# Sheet1.net
KiCad netlist of a schematic drawn in Altium Designer
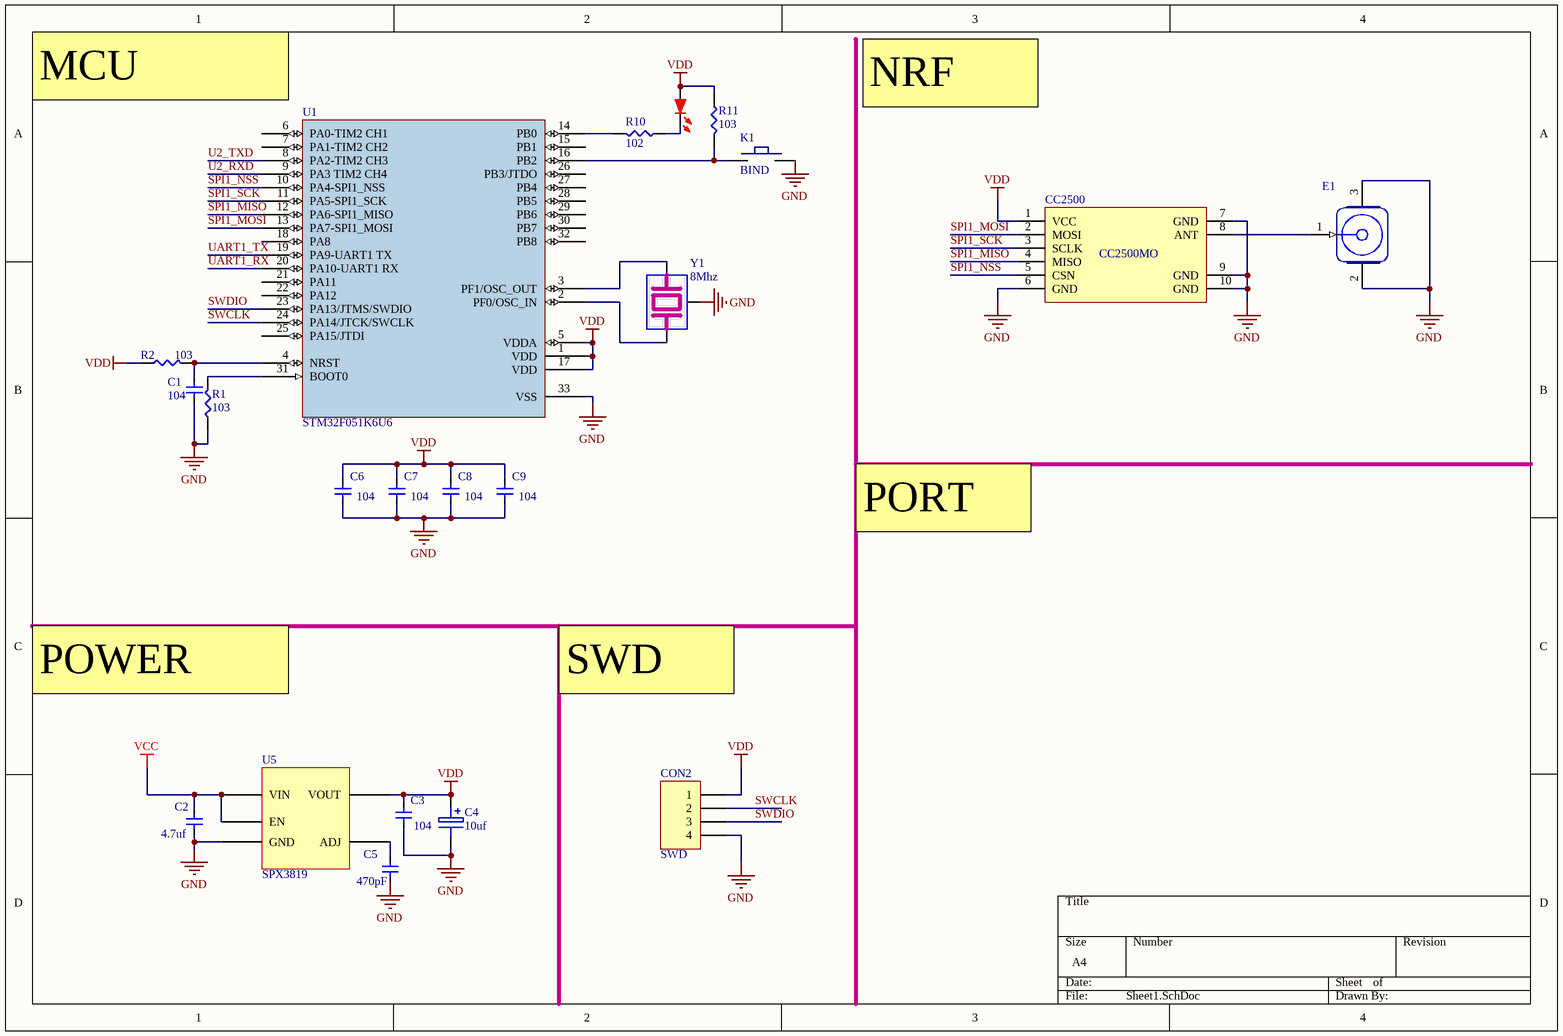
[diagram p0: Sheet1.SchDoc]

(export (version "E")
  (design (tool "Eeschema 10.0.6"))
  (components
    (comp (ref "C1")
      (value "104")
      (footprint "JL_PCB:0603C")
      (description "Capacitor")
      (libsource (lib "BASIC Devices") (part "CAP"))
    )
    (comp (ref "C2")
      (value "4.7uf")
      (footprint "JL_PCB:0603C")
      (description "Capacitor")
      (libsource (lib "BASIC Devices") (part "CAP"))
    )
    (comp (ref "C3")
      (value "104")
      (footprint "0603C")
      (description "Capacitor")
      (libsource (lib "BASIC Devices") (part "CAP"))
    )
    (comp (ref "C4")
      (value "10uf")
      (footprint "JL_PCB:1206C")
      (description "Electrolytic Capacitor")
      (libsource (lib "BASIC Devices") (part "ELECTRO1"))
    )
    (comp (ref "C5")
      (value "470pF")
      (footprint "JL_PCB:0603C")
      (description "Capacitor")
      (libsource (lib "BASIC Devices") (part "CAP"))
    )
    (comp (ref "C6")
      (value "104")
      (footprint "JL_PCB:0603C")
      (description "Capacitor")
      (libsource (lib "BASIC Devices") (part "CAP"))
    )
    (comp (ref "C7")
      (value "104")
      (footprint "JL_PCB:0603C")
      (description "Capacitor")
      (libsource (lib "BASIC Devices") (part "CAP"))
    )
    (comp (ref "C8")
      (value "104")
      (footprint "JL_PCB:0603C")
      (description "Capacitor")
      (libsource (lib "BASIC Devices") (part "CAP"))
    )
    (comp (ref "C9")
      (value "104")
      (footprint "JL_PCB:0603C")
      (description "Capacitor")
      (libsource (lib "BASIC Devices") (part "CAP"))
    )
    (comp (ref "CC2500") (value "CC2500") (libsource (lib "FrSky_Rx_Mini") (part "CC2500")))
    (comp (ref "CON2")
      (value "SWD")
      (footprint "HDR1X4")
      (description "Header, 4-Pin")
      (fields (field (name "PUBLISHER") "Altium Limited"))
      (libsource (lib "3D") (part "Header 4"))
    )
    (comp (ref "D1") (value "LED-R") (footprint "0603C") (libsource (lib "JL_SCH") (part "LED-R")))
    (comp (ref "E1")
      (value "U.FL-LP Hirose Micro RF Connector")
      (footprint "U.FL-LP(V)-040")
      (description "Hirose U.FL-LP(V)-040  Micro RF connector,  50 Ohm Impedance")
      (fields (field (name "MANUFACTURER") "Hirose"))
      (libsource (lib "RF Connectors") (part "U.FL-LP(V)-040"))
    )
    (comp (ref "K1") (value "BIND") (footprint "KEY_3x3x2mm") (libsource (lib "My_lib_wjt") (part "KEY")))
    (comp (ref "R1") (value "103") (footprint "JL_PCB:0603R") (libsource (lib "BASIC Devices") (part "RES0")))
    (comp (ref "R2") (value "103") (footprint "JL_PCB:0603R") (libsource (lib "BASIC Devices") (part "RES0")))
    (comp (ref "R10")
      (value "102")
      (footprint "JL_PCB:0603R")
      (libsource (lib "BASIC Devices") (part "RES0"))
    )
    (comp (ref "R11")
      (value "103")
      (footprint "JL_PCB:0603R")
      (libsource (lib "BASIC Devices") (part "RES0"))
    )
    (comp (ref "U1")
      (value "STM32F051K6U6")
      (footprint "QFN32_1GND")
      (description "STM32 ARM-based 32-bit MCU with 128 Kbytes Flash, 48-pin LQFP, Industrial Temperature")
      (fields (field (name "PUBLISHER") "Altium Limited"))
      (libsource (lib "PCB_Project") (part "STM32F103CBT6"))
    )
    (comp (ref "U5") (value "SPX3819") (footprint "SOT-23-5") (libsource (lib "minifly") (part "SPX3819")))
    (comp (ref "Y1") (value "8Mhz") (footprint "XTAL_mini") (libsource (lib "minifly") (part "XTAL")))
  )
  (nets
    (net (code "1") (name "/SPI1_MISO") (class "Default")
      (node (ref "CC2500") (pin "4") (pinfunction "MISO_4") (pintype "passive"))
      (node (ref "U1") (pin "12") (pinfunction "PA6-SPI1_MISO_12") (pintype "bidirectional"))
    )
    (net (code "2") (name "/SPI1_MOSI") (class "Default")
      (node (ref "CC2500") (pin "2") (pinfunction "MOSI_2") (pintype "passive"))
      (node (ref "U1") (pin "13") (pinfunction "PA7-SPI1_MOSI_13") (pintype "bidirectional"))
    )
    (net (code "3") (name "/SPI1_NSS") (class "Default")
      (node (ref "CC2500") (pin "5") (pinfunction "CSN_5") (pintype "passive"))
      (node (ref "U1") (pin "10") (pinfunction "PA4-SPI1_NSS_10") (pintype "bidirectional"))
    )
    (net (code "4") (name "/SPI1_SCK") (class "Default")
      (node (ref "CC2500") (pin "3") (pinfunction "SCLK_3") (pintype "passive"))
      (node (ref "U1") (pin "11") (pinfunction "PA5-SPI1_SCK_11") (pintype "bidirectional"))
    )
    (net (code "5") (name "/SWCLK") (class "Default")
      (node (ref "CON2") (pin "2") (pinfunction "2_2") (pintype "passive"))
      (node (ref "U1") (pin "24") (pinfunction "PA14/JTCK/SWCLK_24") (pintype "bidirectional"))
    )
    (net (code "6") (name "/SWDIO") (class "Default")
      (node (ref "CON2") (pin "3") (pinfunction "3_3") (pintype "passive"))
      (node (ref "U1") (pin "23") (pinfunction "PA13/JTMS/SWDIO_23") (pintype "bidirectional"))
    )
    (net (code "7") (name "/U2_RXD") (class "Default")
      (node (ref "U1") (pin "9") (pinfunction "PA3_TIM2_CH4_9") (pintype "bidirectional"))
    )
    (net (code "8") (name "/U2_TXD") (class "Default")
      (node (ref "U1") (pin "8") (pinfunction "PA2-TIM2_CH3_8") (pintype "bidirectional"))
    )
    (net (code "9") (name "/UART1_RX") (class "Default")
      (node (ref "U1") (pin "20") (pinfunction "PA10-UART1_RX_20") (pintype "bidirectional"))
    )
    (net (code "10") (name "/UART1_TX") (class "Default")
      (node (ref "U1") (pin "19") (pinfunction "PA9-UART1_TX_19") (pintype "bidirectional"))
    )
    (net (code "11") (name "GND") (class "Default")
      (node (ref "C1") (pin "2") (pinfunction "2_2") (pintype "passive"))
      (node (ref "C2") (pin "2") (pinfunction "2_2") (pintype "passive"))
      (node (ref "C3") (pin "2") (pinfunction "2_2") (pintype "passive"))
      (node (ref "C4") (pin "2") (pinfunction "2_2") (pintype "passive"))
      (node (ref "C5") (pin "2") (pinfunction "2_2") (pintype "passive"))
      (node (ref "C6") (pin "2") (pinfunction "2_2") (pintype "passive"))
      (node (ref "C7") (pin "2") (pinfunction "2_2") (pintype "passive"))
      (node (ref "C8") (pin "2") (pinfunction "2_2") (pintype "passive"))
      (node (ref "C9") (pin "2") (pinfunction "2_2") (pintype "passive"))
      (node (ref "CC2500") (pin "10") (pinfunction "GND_10") (pintype "passive"))
      (node (ref "CC2500") (pin "6") (pinfunction "GND_6") (pintype "passive"))
      (node (ref "CC2500") (pin "7") (pinfunction "GND_7") (pintype "passive"))
      (node (ref "CC2500") (pin "9") (pinfunction "GND_9") (pintype "passive"))
      (node (ref "CON2") (pin "4") (pinfunction "4_4") (pintype "passive"))
      (node (ref "E1") (pin "2") (pinfunction "GND_2") (pintype "power_in"))
      (node (ref "E1") (pin "3") (pinfunction "GND_3") (pintype "power_in"))
      (node (ref "K1") (pin "2") (pinfunction "2_2") (pintype "passive"))
      (node (ref "R1") (pin "1") (pinfunction "1_1") (pintype "passive"))
      (node (ref "U1") (pin "33") (pinfunction "VSS_33") (pintype "power_in"))
      (node (ref "U5") (pin "2") (pinfunction "GND_2") (pintype "passive"))
      (node (ref "Y1") (pin "2") (pinfunction "2_2") (pintype "passive"))
    )
    (net (code "12") (name "Net-(CC2500-ANT)") (class "Default")
      (node (ref "CC2500") (pin "8") (pinfunction "ANT_8") (pintype "passive"))
      (node (ref "E1") (pin "1") (pinfunction "Signal_1") (pintype "input"))
    )
    (net (code "13") (name "Net-(D1-K)") (class "Default")
      (node (ref "D1") (pin "2") (pinfunction "K_2") (pintype "passive"))
      (node (ref "R10") (pin "1") (pinfunction "1_1") (pintype "passive"))
    )
    (net (code "14") (name "Net-(U1-BOOT0)") (class "Default")
      (node (ref "R1") (pin "2") (pinfunction "2_2") (pintype "passive"))
      (node (ref "U1") (pin "31") (pinfunction "BOOT0_31") (pintype "input"))
    )
    (net (code "15") (name "Net-(U1-NRST)") (class "Default")
      (node (ref "C1") (pin "1") (pinfunction "1_1") (pintype "passive"))
      (node (ref "R2") (pin "2") (pinfunction "2_2") (pintype "passive"))
      (node (ref "U1") (pin "4") (pinfunction "NRST_4") (pintype "bidirectional"))
    )
    (net (code "16") (name "Net-(U1-PB0)") (class "Default")
      (node (ref "R10") (pin "2") (pinfunction "2_2") (pintype "passive"))
      (node (ref "U1") (pin "14") (pinfunction "PB0_14") (pintype "bidirectional"))
    )
    (net (code "17") (name "Net-(U1-PB2)") (class "Default")
      (node (ref "K1") (pin "1") (pinfunction "1_1") (pintype "passive"))
      (node (ref "R11") (pin "2") (pinfunction "2_2") (pintype "passive"))
      (node (ref "U1") (pin "16") (pinfunction "PB2_16") (pintype "bidirectional"))
    )
    (net (code "18") (name "Net-(U1-PF0{slash}OSC_IN)") (class "Default")
      (node (ref "U1") (pin "2") (pinfunction "PF0/OSC_IN_2") (pintype "bidirectional"))
      (node (ref "Y1") (pin "1") (pinfunction "1_1") (pintype "passive"))
    )
    (net (code "19") (name "Net-(U1-PF1{slash}OSC_OUT)") (class "Default")
      (node (ref "U1") (pin "3") (pinfunction "PF1/OSC_OUT_3") (pintype "bidirectional"))
      (node (ref "Y1") (pin "3") (pinfunction "3_3") (pintype "passive"))
    )
    (net (code "20") (name "Net-(U5-ADJ)") (class "Default")
      (node (ref "C5") (pin "1") (pinfunction "1_1") (pintype "passive"))
      (node (ref "U5") (pin "4") (pinfunction "ADJ_4") (pintype "passive"))
    )
    (net (code "21") (name "VCC") (class "Default")
      (node (ref "C2") (pin "1") (pinfunction "1_1") (pintype "passive"))
      (node (ref "U5") (pin "1") (pinfunction "VIN_1") (pintype "passive"))
      (node (ref "U5") (pin "3") (pinfunction "EN_3") (pintype "passive"))
    )
    (net (code "22") (name "VDD") (class "Default")
      (node (ref "C3") (pin "1") (pinfunction "1_1") (pintype "passive"))
      (node (ref "C4") (pin "1") (pinfunction "1_1") (pintype "passive"))
      (node (ref "C6") (pin "1") (pinfunction "1_1") (pintype "passive"))
      (node (ref "C7") (pin "1") (pinfunction "1_1") (pintype "passive"))
      (node (ref "C8") (pin "1") (pinfunction "1_1") (pintype "passive"))
      (node (ref "C9") (pin "1") (pinfunction "1_1") (pintype "passive"))
      (node (ref "CC2500") (pin "1") (pinfunction "VCC_1") (pintype "passive"))
      (node (ref "CON2") (pin "1") (pinfunction "1_1") (pintype "passive"))
      (node (ref "D1") (pin "1") (pinfunction "A_1") (pintype "passive"))
      (node (ref "R11") (pin "1") (pinfunction "1_1") (pintype "passive"))
      (node (ref "R2") (pin "1") (pinfunction "1_1") (pintype "passive"))
      (node (ref "U1") (pin "1") (pinfunction "VDD_1") (pintype "power_in"))
      (node (ref "U1") (pin "17") (pinfunction "VDD_17") (pintype "power_in"))
      (node (ref "U1") (pin "5") (pinfunction "VDDA_5") (pintype "bidirectional"))
      (node (ref "U5") (pin "5") (pinfunction "VOUT_5") (pintype "passive"))
    )
    (net (code "23") (name "unconnected-(U1-PA0-TIM2_CH1-Pad6)") (class "Default")
      (node (ref "U1") (pin "6") (pinfunction "PA0-TIM2_CH1_6") (pintype "bidirectional"))
    )
    (net (code "24") (name "unconnected-(U1-PA1-TIM2_CH2-Pad7)") (class "Default")
      (node (ref "U1") (pin "7") (pinfunction "PA1-TIM2_CH2_7") (pintype "bidirectional"))
    )
    (net (code "25") (name "unconnected-(U1-PA8-Pad18)") (class "Default")
      (node (ref "U1") (pin "18") (pinfunction "PA8_18") (pintype "bidirectional"))
    )
    (net (code "26") (name "unconnected-(U1-PA11-Pad21)") (class "Default")
      (node (ref "U1") (pin "21") (pinfunction "PA11_21") (pintype "bidirectional"))
    )
    (net (code "27") (name "unconnected-(U1-PA12-Pad22)") (class "Default")
      (node (ref "U1") (pin "22") (pinfunction "PA12_22") (pintype "bidirectional"))
    )
    (net (code "28") (name "unconnected-(U1-PA15{slash}JTDI-Pad25)") (class "Default")
      (node (ref "U1") (pin "25") (pinfunction "PA15/JTDI_25") (pintype "bidirectional"))
    )
    (net (code "29") (name "unconnected-(U1-PB1-Pad15)") (class "Default")
      (node (ref "U1") (pin "15") (pinfunction "PB1_15") (pintype "bidirectional"))
    )
    (net (code "30") (name "unconnected-(U1-PB3{slash}JTDO-Pad26)") (class "Default")
      (node (ref "U1") (pin "26") (pinfunction "PB3/JTDO_26") (pintype "bidirectional"))
    )
    (net (code "31") (name "unconnected-(U1-PB4-Pad27)") (class "Default")
      (node (ref "U1") (pin "27") (pinfunction "PB4_27") (pintype "bidirectional"))
    )
    (net (code "32") (name "unconnected-(U1-PB5-Pad28)") (class "Default")
      (node (ref "U1") (pin "28") (pinfunction "PB5_28") (pintype "bidirectional"))
    )
    (net (code "33") (name "unconnected-(U1-PB6-Pad29)") (class "Default")
      (node (ref "U1") (pin "29") (pinfunction "PB6_29") (pintype "bidirectional"))
    )
    (net (code "34") (name "unconnected-(U1-PB7-Pad30)") (class "Default")
      (node (ref "U1") (pin "30") (pinfunction "PB7_30") (pintype "bidirectional"))
    )
    (net (code "35") (name "unconnected-(U1-PB8-Pad32)") (class "Default")
      (node (ref "U1") (pin "32") (pinfunction "PB8_32") (pintype "bidirectional"))
    )
  )
)
